# Pioneer.net
KiCad netlist of a schematic drawn in Altium Designer
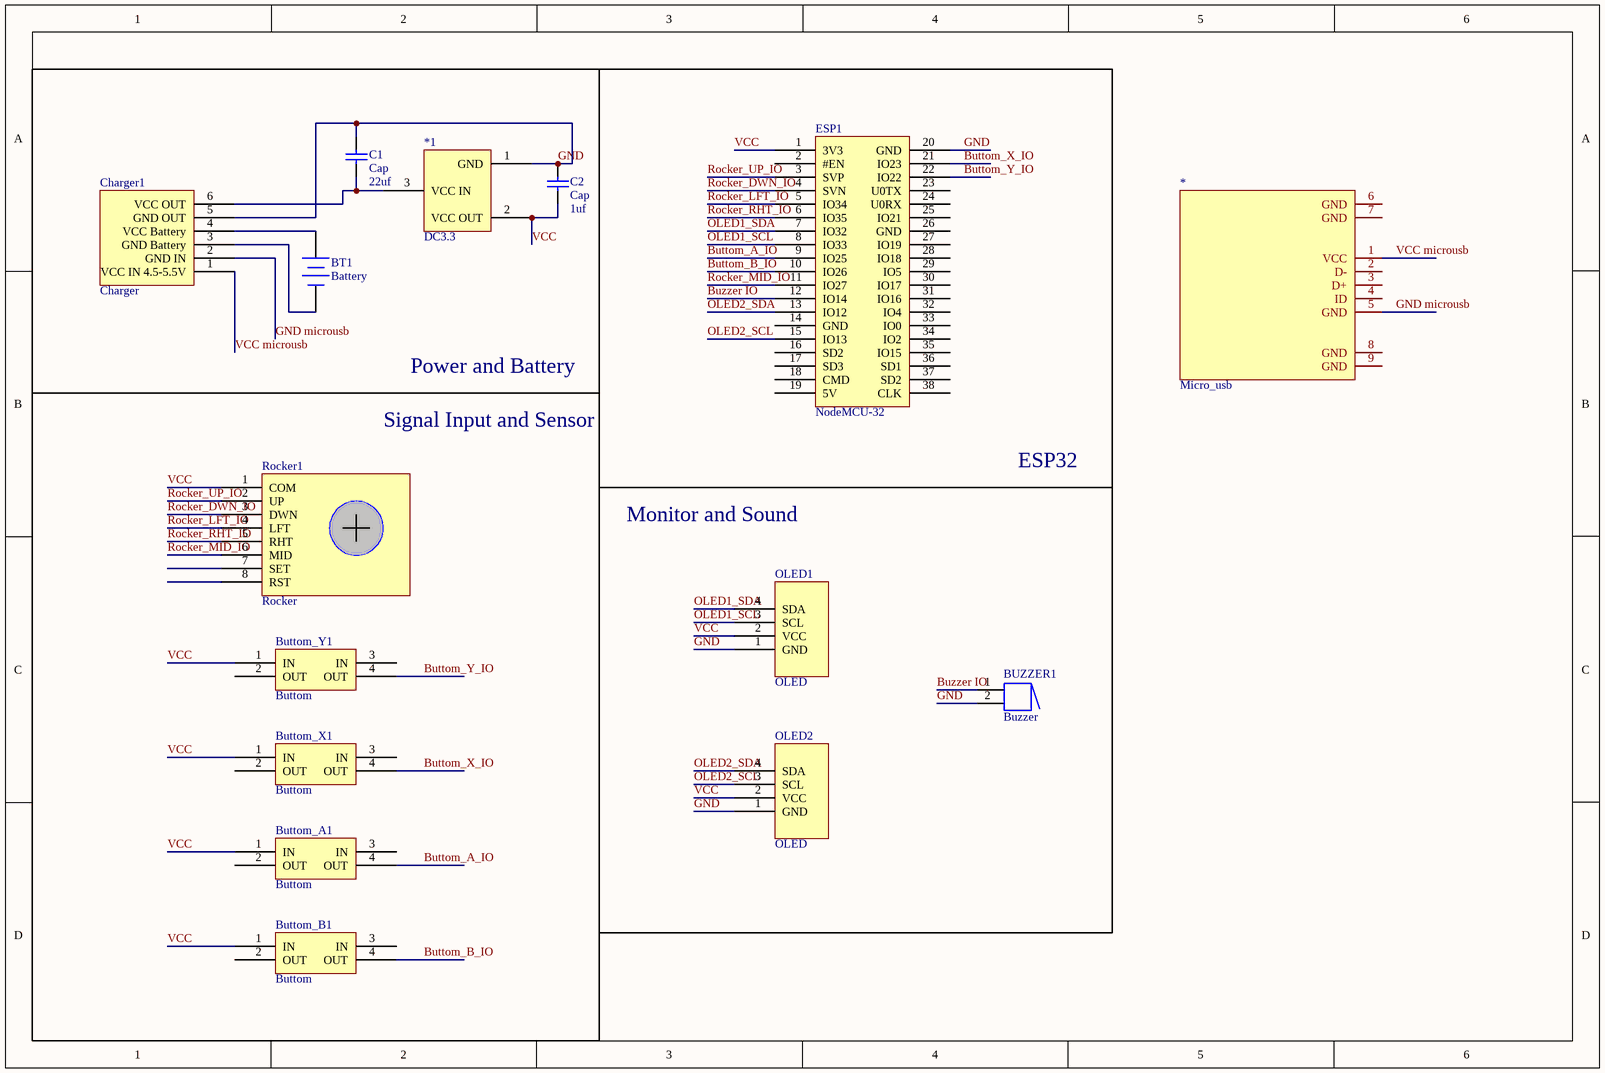
[diagram p0: Pioneer.SchDoc]

(export (version "E")
  (design (tool "Eeschema 10.0.6"))
  (components
    (comp (ref "*")
      (value "Micro_usb")
      (footprint "Micro_usb")
      (libsource (lib "Pioneer_lab") (part "Micro_usb"))
    )
    (comp (ref "*1") (value "DC3.3") (footprint "SOT23_M") (libsource (lib "Pioneer_lab") (part "DC3.3")))
    (comp (ref "BT1")
      (value "Battery")
      (footprint "BAT-2")
      (description "Multicell Battery")
      (fields (field (name "PUBLISHER") "Altium Limited"))
      (libsource (lib "Miscellaneous Devices") (part "Battery"))
    )
    (comp (ref "Buttom_A1")
      (value "Buttom")
      (footprint "Buttom")
      (libsource (lib "Pioneer_lab") (part "Buttom"))
    )
    (comp (ref "Buttom_B1")
      (value "Buttom")
      (footprint "Buttom")
      (libsource (lib "Pioneer_lab") (part "Buttom"))
    )
    (comp (ref "Buttom_X1")
      (value "Buttom")
      (footprint "Buttom")
      (libsource (lib "Pioneer_lab") (part "Buttom"))
    )
    (comp (ref "Buttom_Y1")
      (value "Buttom")
      (footprint "Buttom")
      (libsource (lib "Pioneer_lab") (part "Buttom"))
    )
    (comp (ref "BUZZER1")
      (value "Buzzer")
      (footprint "Buzzer")
      (description "Magnetic Transducer Buzzer")
      (fields (field (name "PUBLISHER") "Altium Limited"))
      (libsource (lib "Miscellaneous Devices") (part "Buzzer"))
    )
    (comp (ref "C1")
      (value "Cap")
      (footprint "0603")
      (description "Capacitor")
      (fields (field (name "ALTIUM_VALUE") "22uf") (field (name "PUBLISHER") "Altium Limited"))
      (libsource (lib "Miscellaneous Devices") (part "Cap"))
    )
    (comp (ref "C2")
      (value "Cap")
      (footprint "0603")
      (description "Capacitor")
      (fields (field (name "ALTIUM_VALUE") "1uf") (field (name "PUBLISHER") "Altium Limited"))
      (libsource (lib "Miscellaneous Devices") (part "Cap"))
    )
    (comp (ref "Charger1")
      (value "Charger")
      (footprint "charge")
      (libsource (lib "Pioneer_lab") (part "Charger"))
    )
    (comp (ref "ESP1")
      (value "NodeMCU-32")
      (footprint "NodeMCU-32")
      (libsource (lib "Pioneer_lab") (part "NodeMCU-32"))
    )
    (comp (ref "OLED1") (value "OLED") (footprint "OLED") (libsource (lib "Pioneer_lab") (part "OLED")))
    (comp (ref "OLED2") (value "OLED") (footprint "OLED") (libsource (lib "Pioneer_lab") (part "OLED")))
    (comp (ref "Rocker1")
      (value "Rocker")
      (footprint "rocker")
      (libsource (lib "Pioneer_lab") (part "Rocker"))
    )
  )
  (nets
    (net (code "1") (name "/Buttom_A_IO") (class "Default")
      (node (ref "Buttom_A1") (pin "4") (pinfunction "OUT_4") (pintype "passive"))
      (node (ref "ESP1") (pin "9") (pinfunction "IO25_9") (pintype "passive"))
    )
    (net (code "2") (name "/Buttom_B_IO") (class "Default")
      (node (ref "Buttom_B1") (pin "4") (pinfunction "OUT_4") (pintype "passive"))
      (node (ref "ESP1") (pin "10") (pinfunction "IO26_10") (pintype "passive"))
    )
    (net (code "3") (name "/Buttom_X_IO") (class "Default")
      (node (ref "Buttom_X1") (pin "4") (pinfunction "OUT_4") (pintype "passive"))
      (node (ref "ESP1") (pin "21") (pinfunction "IO23_21") (pintype "passive"))
    )
    (net (code "4") (name "/Buttom_Y_IO") (class "Default")
      (node (ref "Buttom_Y1") (pin "4") (pinfunction "OUT_4") (pintype "passive"))
      (node (ref "ESP1") (pin "22") (pinfunction "IO22_22") (pintype "passive"))
    )
    (net (code "5") (name "/Buzzer IO") (class "Default")
      (node (ref "BUZZER1") (pin "1") (pinfunction "1_1") (pintype "passive"))
      (node (ref "ESP1") (pin "12") (pinfunction "IO14_12") (pintype "passive"))
    )
    (net (code "6") (name "/GND") (class "Default")
      (node (ref "*1") (pin "1") (pinfunction "GND_1") (pintype "passive"))
      (node (ref "BUZZER1") (pin "2") (pinfunction "2_2") (pintype "passive"))
      (node (ref "C1") (pin "2") (pinfunction "2_2") (pintype "passive"))
      (node (ref "C2") (pin "2") (pinfunction "2_2") (pintype "passive"))
      (node (ref "Charger1") (pin "5") (pinfunction "GND_OUT_5") (pintype "passive"))
      (node (ref "ESP1") (pin "20") (pinfunction "GND_20") (pintype "passive"))
      (node (ref "OLED1") (pin "1") (pinfunction "GND_1") (pintype "passive"))
      (node (ref "OLED2") (pin "1") (pinfunction "GND_1") (pintype "passive"))
    )
    (net (code "7") (name "/GND microusb") (class "Default")
      (node (ref "*") (pin "5") (pinfunction "GND_5") (pintype "passive"))
      (node (ref "Charger1") (pin "2") (pinfunction "GND_IN_2") (pintype "passive"))
    )
    (net (code "8") (name "/OLED1_SCL") (class "Default")
      (node (ref "ESP1") (pin "8") (pinfunction "IO33_8") (pintype "passive"))
      (node (ref "OLED1") (pin "3") (pinfunction "SCL_3") (pintype "passive"))
    )
    (net (code "9") (name "/OLED1_SDA") (class "Default")
      (node (ref "ESP1") (pin "7") (pinfunction "IO32_7") (pintype "passive"))
      (node (ref "OLED1") (pin "4") (pinfunction "SDA_4") (pintype "passive"))
    )
    (net (code "10") (name "/OLED2_SCL") (class "Default")
      (node (ref "ESP1") (pin "15") (pinfunction "IO13_15") (pintype "passive"))
      (node (ref "OLED2") (pin "3") (pinfunction "SCL_3") (pintype "passive"))
    )
    (net (code "11") (name "/OLED2_SDA") (class "Default")
      (node (ref "ESP1") (pin "13") (pinfunction "IO12_13") (pintype "passive"))
      (node (ref "OLED2") (pin "4") (pinfunction "SDA_4") (pintype "passive"))
    )
    (net (code "12") (name "/Rocker_DWN_IO") (class "Default")
      (node (ref "ESP1") (pin "4") (pinfunction "SVN_4") (pintype "passive"))
      (node (ref "Rocker1") (pin "3") (pinfunction "DWN_3") (pintype "passive"))
    )
    (net (code "13") (name "/Rocker_LFT_IO") (class "Default")
      (node (ref "ESP1") (pin "5") (pinfunction "IO34_5") (pintype "passive"))
      (node (ref "Rocker1") (pin "4") (pinfunction "LFT_4") (pintype "passive"))
    )
    (net (code "14") (name "/Rocker_MID_IO") (class "Default")
      (node (ref "ESP1") (pin "11") (pinfunction "IO27_11") (pintype "passive"))
      (node (ref "Rocker1") (pin "6") (pinfunction "MID_6") (pintype "passive"))
    )
    (net (code "15") (name "/Rocker_RHT_IO") (class "Default")
      (node (ref "ESP1") (pin "6") (pinfunction "IO35_6") (pintype "passive"))
      (node (ref "Rocker1") (pin "5") (pinfunction "RHT_5") (pintype "passive"))
    )
    (net (code "16") (name "/Rocker_UP_IO") (class "Default")
      (node (ref "ESP1") (pin "3") (pinfunction "SVP_3") (pintype "passive"))
      (node (ref "Rocker1") (pin "2") (pinfunction "UP_2") (pintype "passive"))
    )
    (net (code "17") (name "/VCC") (class "Default")
      (node (ref "*1") (pin "2") (pinfunction "VCC_OUT_2") (pintype "passive"))
      (node (ref "Buttom_A1") (pin "1") (pinfunction "IN_1") (pintype "passive"))
      (node (ref "Buttom_B1") (pin "1") (pinfunction "IN_1") (pintype "passive"))
      (node (ref "Buttom_X1") (pin "1") (pinfunction "IN_1") (pintype "passive"))
      (node (ref "Buttom_Y1") (pin "1") (pinfunction "IN_1") (pintype "passive"))
      (node (ref "C2") (pin "1") (pinfunction "1_1") (pintype "passive"))
      (node (ref "ESP1") (pin "1") (pinfunction "3V3_1") (pintype "passive"))
      (node (ref "OLED1") (pin "2") (pinfunction "VCC_2") (pintype "passive"))
      (node (ref "OLED2") (pin "2") (pinfunction "VCC_2") (pintype "passive"))
      (node (ref "Rocker1") (pin "1") (pinfunction "COM_1") (pintype "passive"))
    )
    (net (code "18") (name "/VCC microusb") (class "Default")
      (node (ref "*") (pin "1") (pinfunction "VCC_1") (pintype "passive"))
      (node (ref "Charger1") (pin "1") (pinfunction "VCC_IN_4.5-5.5V_1") (pintype "passive"))
    )
    (net (code "19") (name "Net-(*1-VCC_IN)") (class "Default")
      (node (ref "*1") (pin "3") (pinfunction "VCC_IN_3") (pintype "passive"))
      (node (ref "C1") (pin "1") (pinfunction "1_1") (pintype "passive"))
      (node (ref "Charger1") (pin "6") (pinfunction "VCC_OUT_6") (pintype "passive"))
    )
    (net (code "20") (name "Net-(BT1-+)") (class "Default")
      (node (ref "BT1") (pin "1") (pinfunction "+_1") (pintype "passive"))
      (node (ref "Charger1") (pin "4") (pinfunction "VCC_Battery_4") (pintype "passive"))
    )
    (net (code "21") (name "Net-(BT1--)") (class "Default")
      (node (ref "BT1") (pin "2") (pinfunction "-_2") (pintype "passive"))
      (node (ref "Charger1") (pin "3") (pinfunction "GND_Battery_3") (pintype "passive"))
    )
    (net (code "22") (name "unconnected-(*-D+-Pad3)") (class "Default")
      (node (ref "*") (pin "3") (pinfunction "D+_3") (pintype "passive"))
    )
    (net (code "23") (name "unconnected-(*-D--Pad2)") (class "Default")
      (node (ref "*") (pin "2") (pinfunction "D-_2") (pintype "passive"))
    )
    (net (code "24") (name "unconnected-(*-GND-Pad6)") (class "Default")
      (node (ref "*") (pin "6") (pinfunction "GND_6") (pintype "passive"))
    )
    (net (code "25") (name "unconnected-(*-GND-Pad7)") (class "Default")
      (node (ref "*") (pin "7") (pinfunction "GND_7") (pintype "passive"))
    )
    (net (code "26") (name "unconnected-(*-GND-Pad8)") (class "Default")
      (node (ref "*") (pin "8") (pinfunction "GND_8") (pintype "passive"))
    )
    (net (code "27") (name "unconnected-(*-GND-Pad9)") (class "Default")
      (node (ref "*") (pin "9") (pinfunction "GND_9") (pintype "passive"))
    )
    (net (code "28") (name "unconnected-(*-ID-Pad4)") (class "Default")
      (node (ref "*") (pin "4") (pinfunction "ID_4") (pintype "passive"))
    )
    (net (code "29") (name "unconnected-(Buttom_A1-IN-Pad3)") (class "Default")
      (node (ref "Buttom_A1") (pin "3") (pinfunction "IN_3") (pintype "passive"))
    )
    (net (code "30") (name "unconnected-(Buttom_A1-OUT-Pad2)") (class "Default")
      (node (ref "Buttom_A1") (pin "2") (pinfunction "OUT_2") (pintype "passive"))
    )
    (net (code "31") (name "unconnected-(Buttom_B1-IN-Pad3)") (class "Default")
      (node (ref "Buttom_B1") (pin "3") (pinfunction "IN_3") (pintype "passive"))
    )
    (net (code "32") (name "unconnected-(Buttom_B1-OUT-Pad2)") (class "Default")
      (node (ref "Buttom_B1") (pin "2") (pinfunction "OUT_2") (pintype "passive"))
    )
    (net (code "33") (name "unconnected-(Buttom_X1-IN-Pad3)") (class "Default")
      (node (ref "Buttom_X1") (pin "3") (pinfunction "IN_3") (pintype "passive"))
    )
    (net (code "34") (name "unconnected-(Buttom_X1-OUT-Pad2)") (class "Default")
      (node (ref "Buttom_X1") (pin "2") (pinfunction "OUT_2") (pintype "passive"))
    )
    (net (code "35") (name "unconnected-(Buttom_Y1-IN-Pad3)") (class "Default")
      (node (ref "Buttom_Y1") (pin "3") (pinfunction "IN_3") (pintype "passive"))
    )
    (net (code "36") (name "unconnected-(Buttom_Y1-OUT-Pad2)") (class "Default")
      (node (ref "Buttom_Y1") (pin "2") (pinfunction "OUT_2") (pintype "passive"))
    )
    (net (code "37") (name "unconnected-(ESP1-#EN-Pad2)") (class "Default")
      (node (ref "ESP1") (pin "2") (pinfunction "#EN_2") (pintype "passive"))
    )
    (net (code "38") (name "unconnected-(ESP1-5V-Pad19)") (class "Default")
      (node (ref "ESP1") (pin "19") (pinfunction "5V_19") (pintype "passive"))
    )
    (net (code "39") (name "unconnected-(ESP1-CLK-Pad38)") (class "Default")
      (node (ref "ESP1") (pin "38") (pinfunction "CLK_38") (pintype "passive"))
    )
    (net (code "40") (name "unconnected-(ESP1-CMD-Pad18)") (class "Default")
      (node (ref "ESP1") (pin "18") (pinfunction "CMD_18") (pintype "passive"))
    )
    (net (code "41") (name "unconnected-(ESP1-GND-Pad14)") (class "Default")
      (node (ref "ESP1") (pin "14") (pinfunction "GND_14") (pintype "passive"))
    )
    (net (code "42") (name "unconnected-(ESP1-GND-Pad26)") (class "Default")
      (node (ref "ESP1") (pin "26") (pinfunction "GND_26") (pintype "passive"))
    )
    (net (code "43") (name "unconnected-(ESP1-IO0-Pad33)") (class "Default")
      (node (ref "ESP1") (pin "33") (pinfunction "IO0_33") (pintype "passive"))
    )
    (net (code "44") (name "unconnected-(ESP1-IO2-Pad34)") (class "Default")
      (node (ref "ESP1") (pin "34") (pinfunction "IO2_34") (pintype "passive"))
    )
    (net (code "45") (name "unconnected-(ESP1-IO4-Pad32)") (class "Default")
      (node (ref "ESP1") (pin "32") (pinfunction "IO4_32") (pintype "passive"))
    )
    (net (code "46") (name "unconnected-(ESP1-IO5-Pad29)") (class "Default")
      (node (ref "ESP1") (pin "29") (pinfunction "IO5_29") (pintype "passive"))
    )
    (net (code "47") (name "unconnected-(ESP1-IO15-Pad35)") (class "Default")
      (node (ref "ESP1") (pin "35") (pinfunction "IO15_35") (pintype "passive"))
    )
    (net (code "48") (name "unconnected-(ESP1-IO16-Pad31)") (class "Default")
      (node (ref "ESP1") (pin "31") (pinfunction "IO16_31") (pintype "passive"))
    )
    (net (code "49") (name "unconnected-(ESP1-IO17-Pad30)") (class "Default")
      (node (ref "ESP1") (pin "30") (pinfunction "IO17_30") (pintype "passive"))
    )
    (net (code "50") (name "unconnected-(ESP1-IO18-Pad28)") (class "Default")
      (node (ref "ESP1") (pin "28") (pinfunction "IO18_28") (pintype "passive"))
    )
    (net (code "51") (name "unconnected-(ESP1-IO19-Pad27)") (class "Default")
      (node (ref "ESP1") (pin "27") (pinfunction "IO19_27") (pintype "passive"))
    )
    (net (code "52") (name "unconnected-(ESP1-IO21-Pad25)") (class "Default")
      (node (ref "ESP1") (pin "25") (pinfunction "IO21_25") (pintype "passive"))
    )
    (net (code "53") (name "unconnected-(ESP1-SD1-Pad36)") (class "Default")
      (node (ref "ESP1") (pin "36") (pinfunction "SD1_36") (pintype "passive"))
    )
    (net (code "54") (name "unconnected-(ESP1-SD2-Pad16)") (class "Default")
      (node (ref "ESP1") (pin "16") (pinfunction "SD2_16") (pintype "passive"))
    )
    (net (code "55") (name "unconnected-(ESP1-SD2-Pad37)") (class "Default")
      (node (ref "ESP1") (pin "37") (pinfunction "SD2_37") (pintype "passive"))
    )
    (net (code "56") (name "unconnected-(ESP1-SD3-Pad17)") (class "Default")
      (node (ref "ESP1") (pin "17") (pinfunction "SD3_17") (pintype "passive"))
    )
    (net (code "57") (name "unconnected-(ESP1-U0RX-Pad24)") (class "Default")
      (node (ref "ESP1") (pin "24") (pinfunction "U0RX_24") (pintype "passive"))
    )
    (net (code "58") (name "unconnected-(ESP1-U0TX-Pad23)") (class "Default")
      (node (ref "ESP1") (pin "23") (pinfunction "U0TX_23") (pintype "passive"))
    )
    (net (code "59") (name "unconnected-(Rocker1-RST-Pad8)") (class "Default")
      (node (ref "Rocker1") (pin "8") (pinfunction "RST_8") (pintype "passive"))
    )
    (net (code "60") (name "unconnected-(Rocker1-SET-Pad7)") (class "Default")
      (node (ref "Rocker1") (pin "7") (pinfunction "SET_7") (pintype "passive"))
    )
  )
)
